# USBC_PD_PWR.net
KiCad netlist of a schematic drawn in Altium Designer
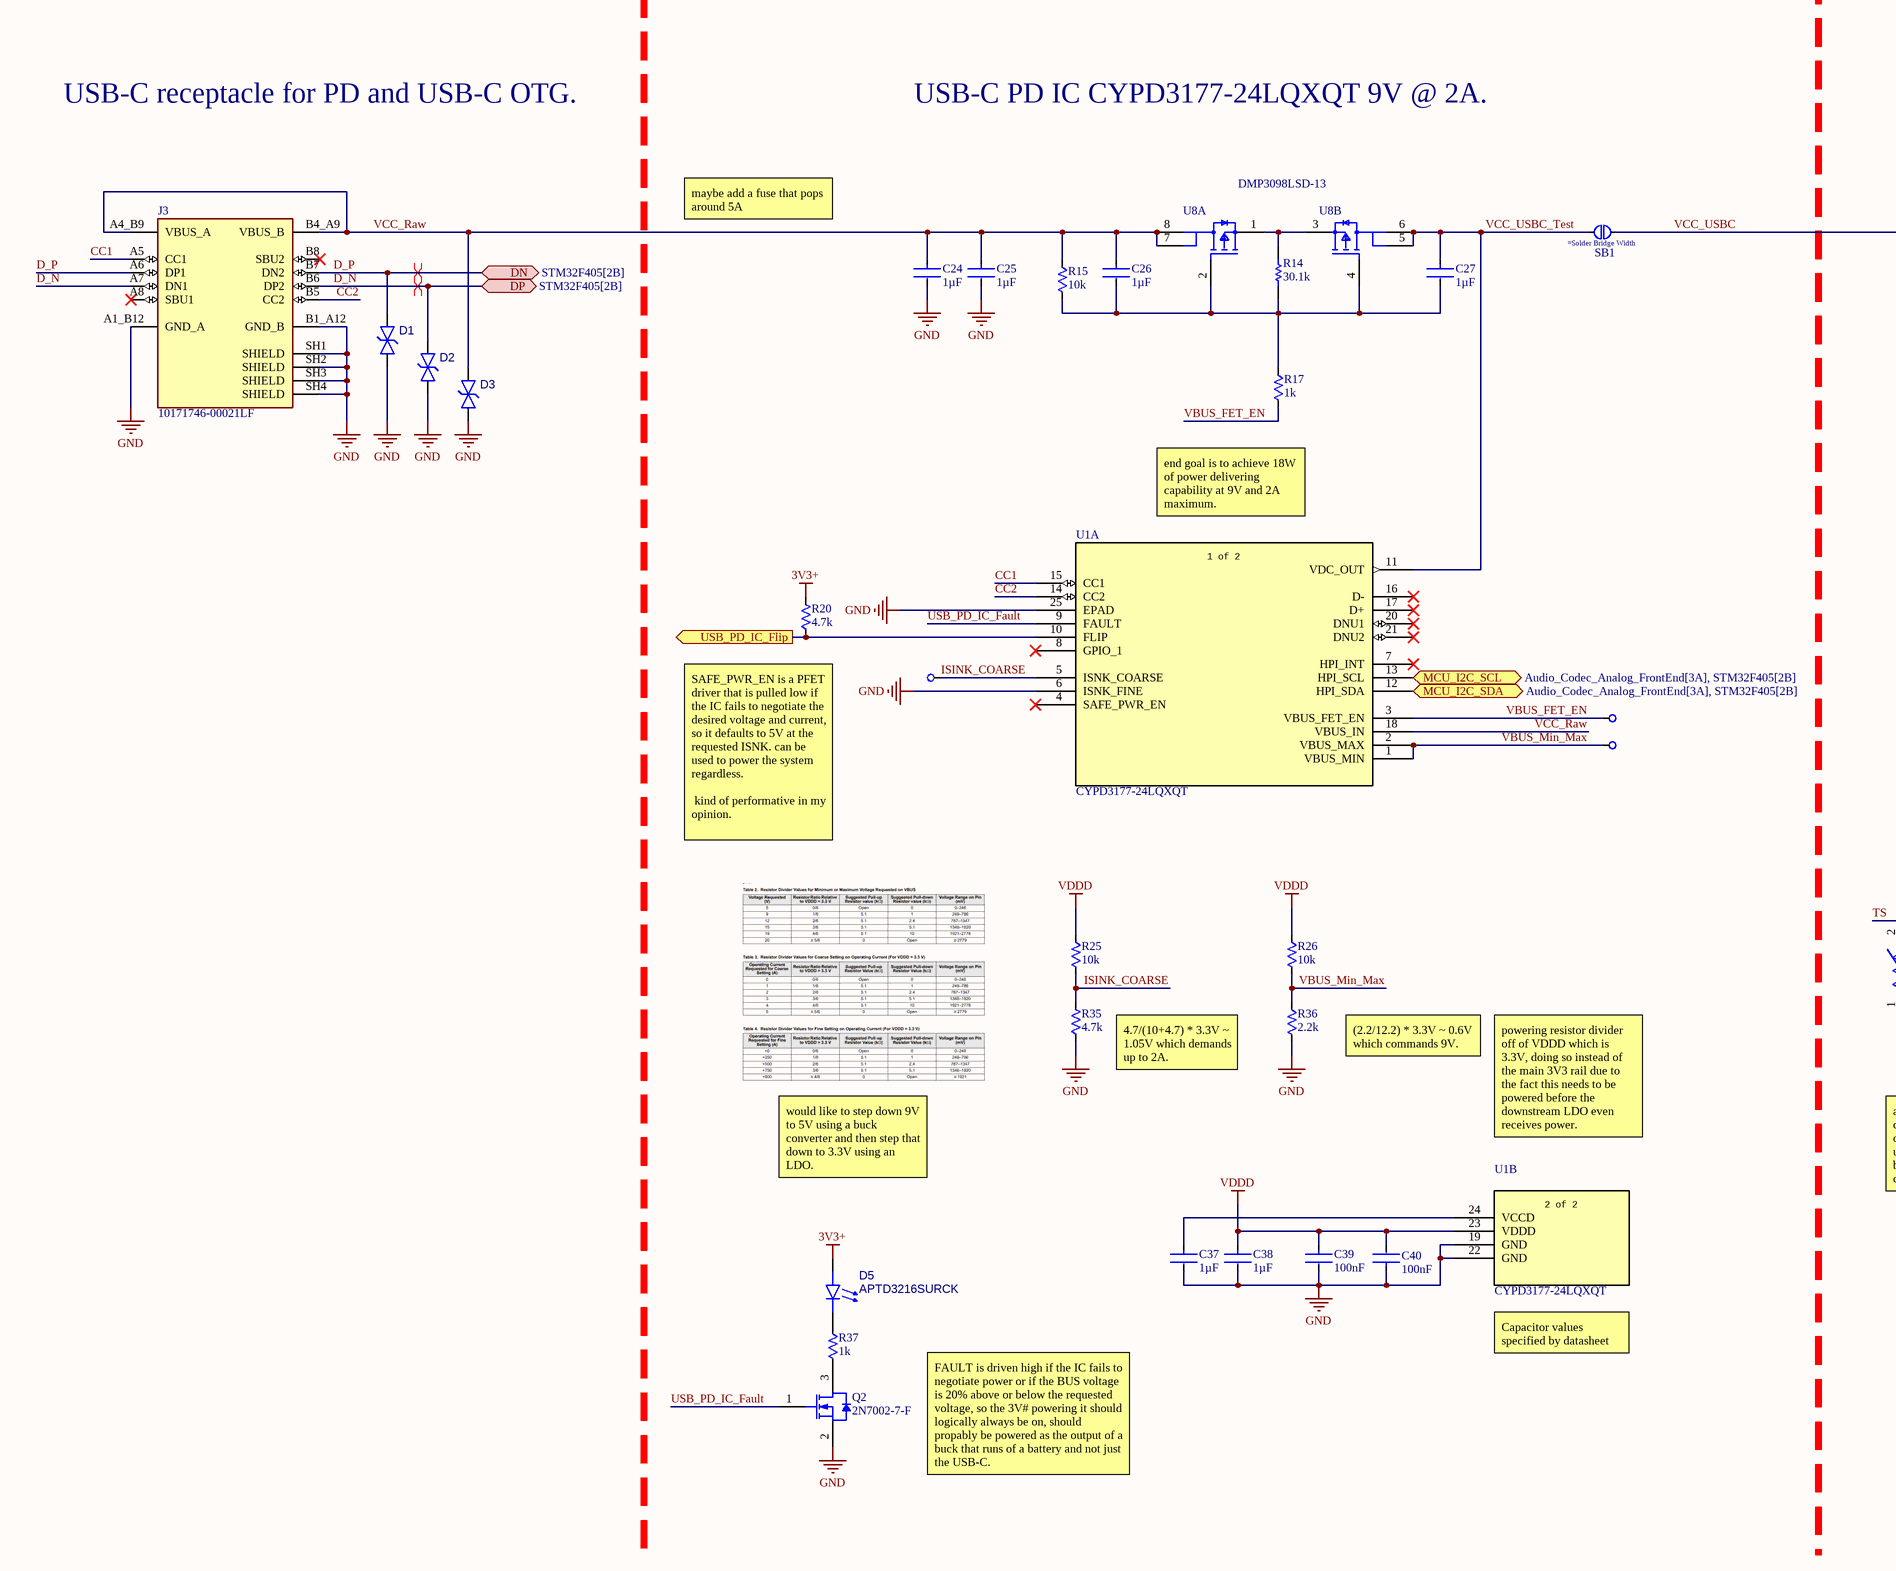
[diagram p0: USBC_PD_PWR.SchDoc, left]
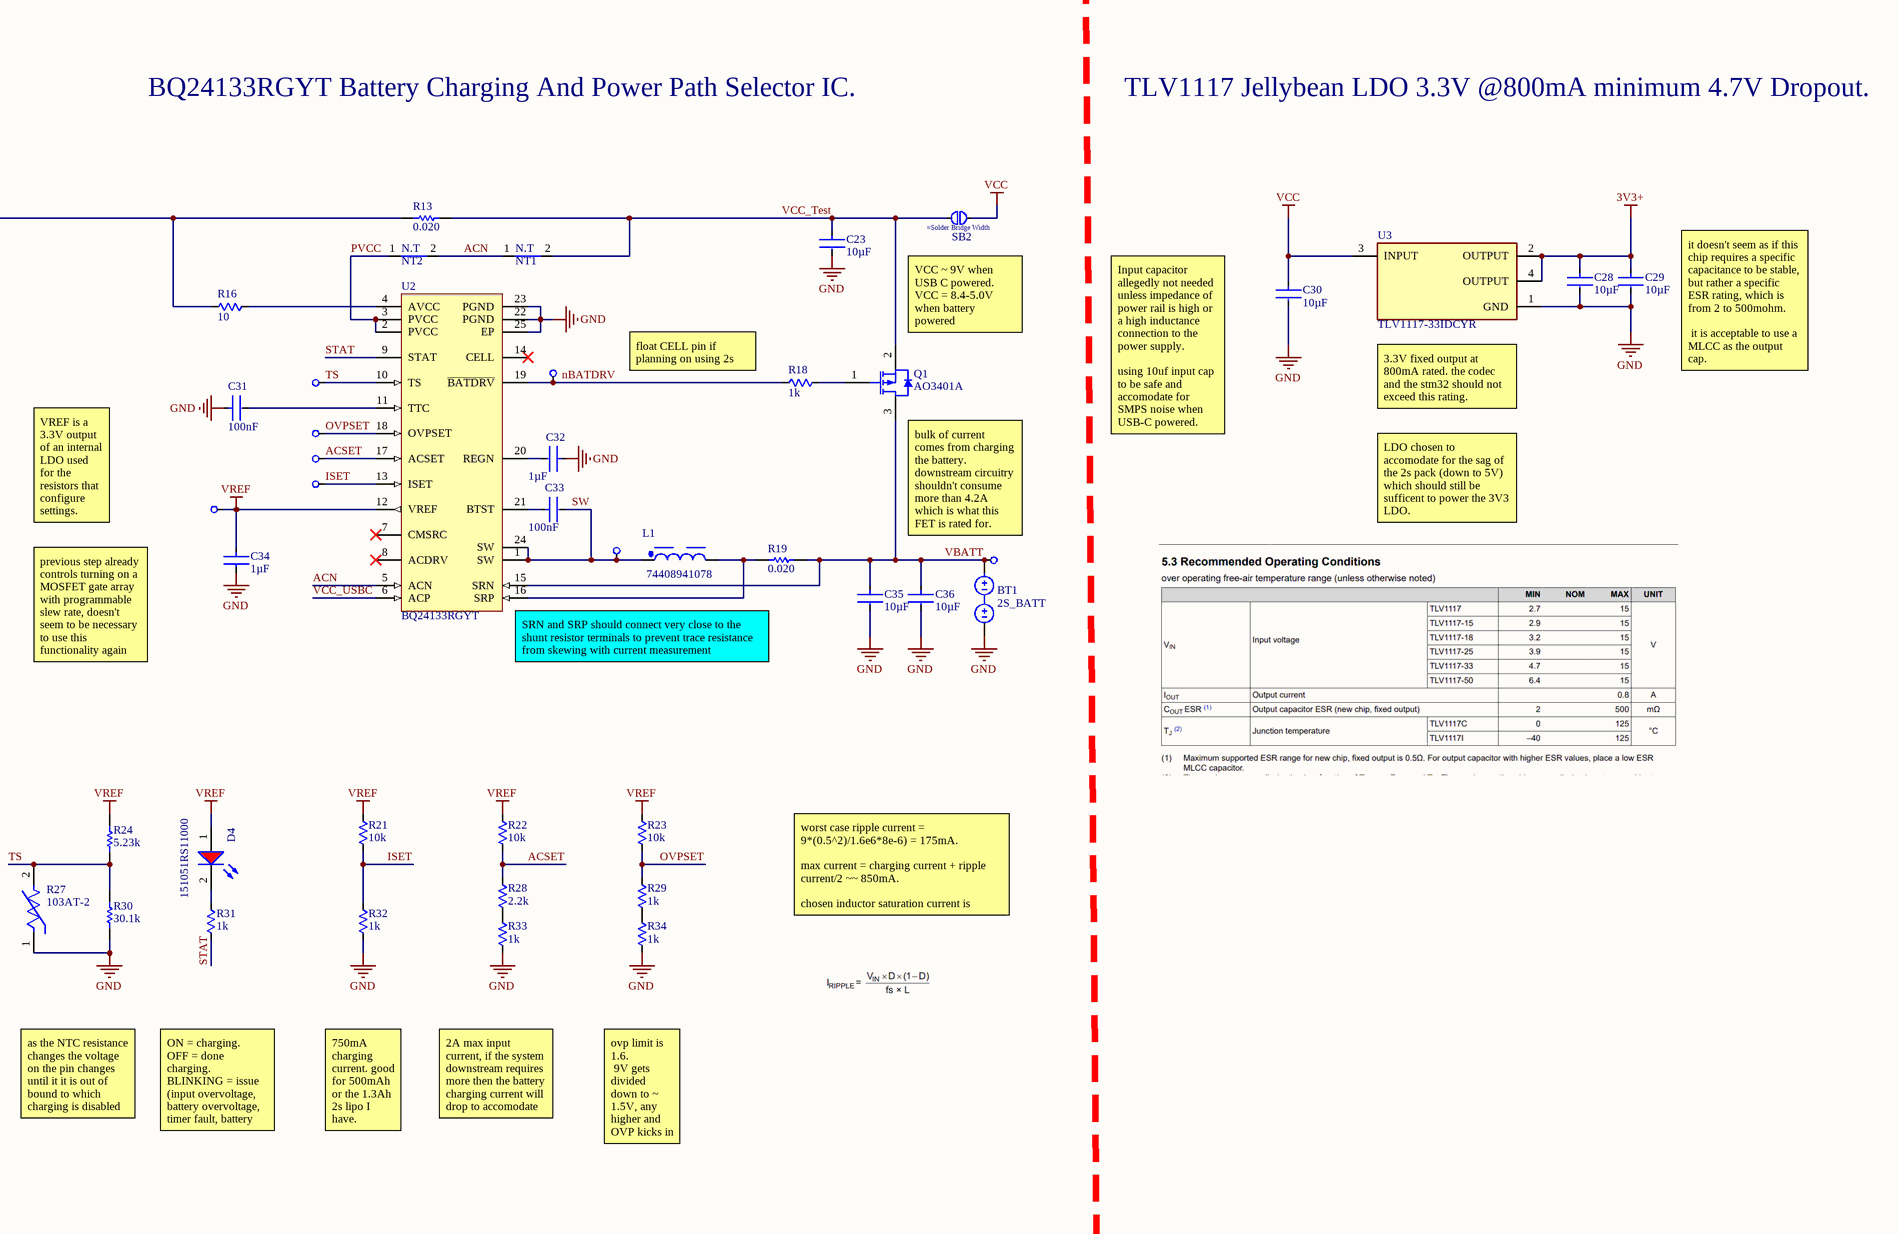
[diagram p1: USBC_PD_PWR.SchDoc, right]

(export (version "E")
  (design (tool "Eeschema 10.0.6"))
  (components
    (comp (ref "BT1")
      (value "2S_BATT")
      (footprint "2_soldering_pads")
      (libsource (lib "main_project_library") (part "2S_BATT"))
    )
    (comp (ref "C23")
      (value "10µF")
      (footprint "MURATA-G_M21B")
      (description "10 µF ±10% 25V Ceramic Capacitor X7S 0805 (2012 Metric)")
      (fields (field (name "TOLERANCE") "10%") (field (name "Comment") "GCM21BC71E106KE36L"))
      (libsource (lib "UCalgary Racing") (part "CAPACITOR"))
    )
    (comp (ref "C24")
      (value "1µF")
      (footprint "MURATA-G_M188")
      (description "1 µF ±10% 25V Ceramic Capacitor X7R 0603 (1608 Metric)")
      (fields (field (name "TOLERANCE") "10%") (field (name "Comment") "GCM188R71E105KA64D"))
      (libsource (lib "UCalgary Racing") (part "CAPACITOR"))
    )
    (comp (ref "C25")
      (value "1µF")
      (footprint "MURATA-G_M188")
      (description "1 µF ±10% 25V Ceramic Capacitor X7R 0603 (1608 Metric)")
      (fields (field (name "TOLERANCE") "10%") (field (name "Comment") "GCM188R71E105KA64D"))
      (libsource (lib "UCalgary Racing") (part "CAPACITOR"))
    )
    (comp (ref "C26")
      (value "1µF")
      (footprint "MURATA-G_M188")
      (description "1 µF ±10% 25V Ceramic Capacitor X7R 0603 (1608 Metric)")
      (fields (field (name "TOLERANCE") "10%") (field (name "Comment") "GCM188R71E105KA64D"))
      (libsource (lib "UCalgary Racing") (part "CAPACITOR"))
    )
    (comp (ref "C27")
      (value "1µF")
      (footprint "MURATA-G_M188")
      (description "1 µF ±10% 25V Ceramic Capacitor X7R 0603 (1608 Metric)")
      (fields (field (name "TOLERANCE") "10%") (field (name "Comment") "GCM188R71E105KA64D"))
      (libsource (lib "UCalgary Racing") (part "CAPACITOR"))
    )
    (comp (ref "C28")
      (value "10µF")
      (footprint "MURATA-G_M21B")
      (description "10 µF ±10% 25V Ceramic Capacitor X7S 0805 (2012 Metric)")
      (fields (field (name "TOLERANCE") "10%") (field (name "Comment") "GCM21BC71E106KE36L"))
      (libsource (lib "UCalgary Racing") (part "CAPACITOR"))
    )
    (comp (ref "C29")
      (value "10µF")
      (footprint "MURATA-G_M21B")
      (description "10 µF ±10% 25V Ceramic Capacitor X7S 0805 (2012 Metric)")
      (fields (field (name "TOLERANCE") "10%") (field (name "Comment") "GCM21BC71E106KE36L"))
      (libsource (lib "UCalgary Racing") (part "CAPACITOR"))
    )
    (comp (ref "C30")
      (value "10µF")
      (footprint "MURATA-G_M21B")
      (description "10 µF ±10% 25V Ceramic Capacitor X7S 0805 (2012 Metric)")
      (fields (field (name "TOLERANCE") "10%") (field (name "Comment") "GCM21BC71E106KE36L"))
      (libsource (lib "UCalgary Racing") (part "CAPACITOR"))
    )
    (comp (ref "C31")
      (value "100nF")
      (footprint "MURATA-G_M188")
      (description "0.1 µF ±10% 50V Ceramic Capacitor X7R 0603 (1608 Metric)")
      (fields (field (name "TOLERANCE") "10%") (field (name "Comment") "GCM188R71H104KA57D"))
      (libsource (lib "UCalgary Racing") (part "CAPACITOR"))
    )
    (comp (ref "C32")
      (value "1µF")
      (footprint "MURATA-G_M188")
      (description "1 µF ±10% 25V Ceramic Capacitor X7R 0603 (1608 Metric)")
      (fields (field (name "TOLERANCE") "10%") (field (name "Comment") "GCM188R71E105KA64D"))
      (libsource (lib "UCalgary Racing") (part "CAPACITOR"))
    )
    (comp (ref "C33")
      (value "100nF")
      (footprint "MURATA-G_M188")
      (description "0.1 µF ±10% 50V Ceramic Capacitor X7R 0603 (1608 Metric)")
      (fields (field (name "TOLERANCE") "10%") (field (name "Comment") "GCM188R71H104KA57D"))
      (libsource (lib "UCalgary Racing") (part "CAPACITOR"))
    )
    (comp (ref "C34")
      (value "1µF")
      (footprint "MURATA-G_M188")
      (description "1 µF ±10% 25V Ceramic Capacitor X7R 0603 (1608 Metric)")
      (fields (field (name "TOLERANCE") "10%") (field (name "Comment") "GCM188R71E105KA64D"))
      (libsource (lib "UCalgary Racing") (part "CAPACITOR"))
    )
    (comp (ref "C35")
      (value "10µF")
      (footprint "MURATA-G_M21B")
      (description "10 µF ±10% 25V Ceramic Capacitor X7S 0805 (2012 Metric)")
      (fields (field (name "TOLERANCE") "10%") (field (name "Comment") "GCM21BC71E106KE36L"))
      (libsource (lib "UCalgary Racing") (part "CAPACITOR"))
    )
    (comp (ref "C36")
      (value "10µF")
      (footprint "MURATA-G_M21B")
      (description "10 µF ±10% 25V Ceramic Capacitor X7S 0805 (2012 Metric)")
      (fields (field (name "TOLERANCE") "10%") (field (name "Comment") "GCM21BC71E106KE36L"))
      (libsource (lib "UCalgary Racing") (part "CAPACITOR"))
    )
    (comp (ref "C37")
      (value "1µF")
      (footprint "MURATA-G_M188")
      (description "1 µF ±10% 25V Ceramic Capacitor X7R 0603 (1608 Metric)")
      (fields (field (name "TOLERANCE") "10%") (field (name "Comment") "GCM188R71E105KA64D"))
      (libsource (lib "UCalgary Racing") (part "CAPACITOR"))
    )
    (comp (ref "C38")
      (value "1µF")
      (footprint "MURATA-G_M188")
      (description "1 µF ±10% 25V Ceramic Capacitor X7R 0603 (1608 Metric)")
      (fields (field (name "TOLERANCE") "10%") (field (name "Comment") "GCM188R71E105KA64D"))
      (libsource (lib "UCalgary Racing") (part "CAPACITOR"))
    )
    (comp (ref "C39")
      (value "100nF")
      (footprint "MURATA-G_M188")
      (description "0.1 µF ±10% 50V Ceramic Capacitor X7R 0603 (1608 Metric)")
      (fields (field (name "TOLERANCE") "10%") (field (name "Comment") "GCM188R71H104KA57D"))
      (libsource (lib "UCalgary Racing") (part "CAPACITOR"))
    )
    (comp (ref "C40")
      (value "100nF")
      (footprint "MURATA-G_M188")
      (description "0.1 µF ±10% 50V Ceramic Capacitor X7R 0603 (1608 Metric)")
      (fields (field (name "TOLERANCE") "10%") (field (name "Comment") "GCM188R71H104KA57D"))
      (libsource (lib "UCalgary Racing") (part "CAPACITOR"))
    )
    (comp (ref "D1")
      (value "SD12C.TCT")
      (footprint "SDXXC.TCT")
      (description "24V Clamp 15A (8/20µs) Ipp Tvs Diode Surface Mount SOD-323")
      (libsource (lib "UCalgary Racing") (part "D-TVS-AA-2"))
    )
    (comp (ref "D2")
      (value "SD12C.TCT")
      (footprint "SDXXC.TCT")
      (description "24V Clamp 15A (8/20µs) Ipp Tvs Diode Surface Mount SOD-323")
      (libsource (lib "UCalgary Racing") (part "D-TVS-AA-2"))
    )
    (comp (ref "D3")
      (value "SD12C.TCT")
      (footprint "SDXXC.TCT")
      (description "24V Clamp 15A (8/20µs) Ipp Tvs Diode Surface Mount SOD-323")
      (libsource (lib "UCalgary Racing") (part "D-TVS-AA-2"))
    )
    (comp (ref "D4")
      (value "151051RS11000")
      (footprint "WL-TMRC_D5.9H8.7")
      (description "WL-TMRC Red Color Diffused 5 mm Round Through Hole LED")
      (libsource (lib "Altium Content Vault") (part "LED_Red_1A-2K"))
    )
    (comp (ref "D5")
      (value "APTD3216SURCK")
      (footprint "APTD3216SURCK-Footprint-1")
      (description "Single Color LED, Hyper Red, Water Clear, 1.6mm")
      (libsource (lib "UCalgary Racing") (part "DIODE-LED-2"))
    )
    (comp (ref "J3")
      (value "10171746-00021LF")
      (footprint "AMPHENOL_10171746-00021LF")
      (fields (field (name "MF") "Amphenol"))
      (libsource (lib "UCalgary Racing") (part "10171746-00021LF"))
    )
    (comp (ref "L1")
      (value "74408941078")
      (footprint "WE-SPC_4818")
      (description "WE-SPC SMT Shielded Power Inductor")
      (libsource (lib "Altium Content Vault") (part "Inductor - 2"))
    )
    (comp (ref "NT1")
      (value "Net_Tie")
      (footprint "Net_Tie_150")
      (libsource (lib "main_project_library") (part "Net_Tie"))
    )
    (comp (ref "NT2")
      (value "Net_Tie")
      (footprint "Net_Tie_150")
      (libsource (lib "main_project_library") (part "Net_Tie"))
    )
    (comp (ref "Q1")
      (value "AO3401A")
      (footprint "AO-SOT-23-3L_V")
      (description "P-Channel MOSFET, 30 V, 4 A, -55 to 150 degC, 3-Pin SOT-23-3L, RoHS, Tape and Reel")
      (fields (field (name "MANUFACTURER") "Alpha and Omega"))
      (libsource (lib "Altium Content Vault") (part "PEMOS-GSD-3"))
    )
    (comp (ref "Q2")
      (value "2N7002-7-F")
      (footprint "DIODESINC-SOT23")
      (description "N-Channel 60 V 115mA (Ta) 370mW (Ta) Surface Mount SOT-23-3")
      (libsource (lib "UCalgary Racing") (part "NMOS_A"))
    )
    (comp (ref "R13")
      (value "0.020")
      (footprint "RESC3216X70X50LL05T20")
      (fields (field (name "MANUFACTURER") "Panasonic") (field (name "PART NUMBER") "ERJ8CWFR020V"))
      (libsource (lib "Altium Content Vault") (part "RES"))
    )
    (comp (ref "R14")
      (value "30.1k")
      (footprint "RESC0603(1608)_N")
      (description "30K1 0.1W 1% 0603 (1608 Metric)  SMD")
      (fields (field (name "TOLERANCE") "1 %") (field (name "POWER") "0.1 W"))
      (libsource (lib "Altium Content Vault") (part "RES"))
    )
    (comp (ref "R15")
      (value "10k")
      (footprint "VISHAY-CRCW0603")
      (description "10 kOhms ±1% 0.1W, 1/10W Chip Resistor 0603 (1608 Metric) Automotive AEC-Q200 Thick Film")
      (fields (field (name "POWER") "100mW") (field (name "TOLERANCE") "1%"))
      (libsource (lib "UCalgary Racing") (part "RESISTOR"))
    )
    (comp (ref "R16")
      (value "10")
      (footprint "FP-CRCW1206-e3-MFG")
      (description "RES SMD 10 OHM 1% 3/4W 1206")
      (fields (field (name "POWER") "750mW") (field (name "TOLERANCE") "1%"))
      (libsource (lib "UCalgary Racing") (part "RESISTOR"))
    )
    (comp (ref "R17")
      (value "1k")
      (footprint "VISHAY-TNPW0603")
      (fields
        (field (name "POWER") "100mW")
        (field (name "TOLERANCE") "0.1%")
        (field (name "Comment") "TNPW06031K00BEEA")
      )
      (libsource (lib "UCalgary Racing") (part "RESISTOR"))
    )
    (comp (ref "R18")
      (value "1k")
      (footprint "VISHAY-TNPW0603")
      (fields
        (field (name "POWER") "100mW")
        (field (name "TOLERANCE") "0.1%")
        (field (name "Comment") "TNPW06031K00BEEA")
      )
      (libsource (lib "UCalgary Racing") (part "RESISTOR"))
    )
    (comp (ref "R19")
      (value "0.020")
      (footprint "RESC3216X70X50LL05T20")
      (fields (field (name "MANUFACTURER") "Panasonic") (field (name "PART NUMBER") "ERJ8CWFR020V"))
      (libsource (lib "Altium Content Vault") (part "RES"))
    )
    (comp (ref "R20")
      (value "4.7k")
      (footprint "VISHAY-CRCW0603")
      (description "4.7 kOhms ±1% 0.1W, 1/10W Chip Resistor 0603 (1608 Metric) Automotive AEC-Q200 Thick Film")
      (fields (field (name "POWER") "100mW") (field (name "TOLERANCE") "1%"))
      (libsource (lib "UCalgary Racing") (part "RESISTOR"))
    )
    (comp (ref "R21")
      (value "10k")
      (footprint "VISHAY-CRCW0603")
      (description "10 kOhms ±1% 0.1W, 1/10W Chip Resistor 0603 (1608 Metric) Automotive AEC-Q200 Thick Film")
      (fields (field (name "POWER") "100mW") (field (name "TOLERANCE") "1%"))
      (libsource (lib "UCalgary Racing") (part "RESISTOR"))
    )
    (comp (ref "R22")
      (value "10k")
      (footprint "VISHAY-CRCW0603")
      (description "10 kOhms ±1% 0.1W, 1/10W Chip Resistor 0603 (1608 Metric) Automotive AEC-Q200 Thick Film")
      (fields (field (name "POWER") "100mW") (field (name "TOLERANCE") "1%"))
      (libsource (lib "UCalgary Racing") (part "RESISTOR"))
    )
    (comp (ref "R23")
      (value "10k")
      (footprint "VISHAY-CRCW0603")
      (description "10 kOhms ±1% 0.1W, 1/10W Chip Resistor 0603 (1608 Metric) Automotive AEC-Q200 Thick Film")
      (fields (field (name "POWER") "100mW") (field (name "TOLERANCE") "1%"))
      (libsource (lib "UCalgary Racing") (part "RESISTOR"))
    )
    (comp (ref "R24")
      (value "5.23k")
      (footprint "RESC1608X55X30NL15T15")
      (fields (field (name "MANUFACTURER") "Panasonic") (field (name "PART NUMBER") "ERJ-3EKF5231V"))
      (libsource (lib "Altium Content Vault") (part "RES"))
    )
    (comp (ref "R25")
      (value "10k")
      (footprint "VISHAY-CRCW0603")
      (description "10 kOhms ±1% 0.1W, 1/10W Chip Resistor 0603 (1608 Metric) Automotive AEC-Q200 Thick Film")
      (fields (field (name "POWER") "100mW") (field (name "TOLERANCE") "1%"))
      (libsource (lib "UCalgary Racing") (part "RESISTOR"))
    )
    (comp (ref "R26")
      (value "10k")
      (footprint "VISHAY-CRCW0603")
      (description "10 kOhms ±1% 0.1W, 1/10W Chip Resistor 0603 (1608 Metric) Automotive AEC-Q200 Thick Film")
      (fields (field (name "POWER") "100mW") (field (name "TOLERANCE") "1%"))
      (libsource (lib "UCalgary Racing") (part "RESISTOR"))
    )
    (comp (ref "R27")
      (value "103AT-2")
      (footprint "FP-103AT-2-MFG")
      (description "Thermistor NTC 10KOhm 1% 2-Pin")
      (fields (field (name "TOLERANCE") "1%"))
      (libsource (lib "Altium Content Vault") (part "3b148a6ebabc5fb4d708a66c052d352"))
    )
    (comp (ref "R28")
      (value "2.2k")
      (footprint "VISHAY-CRCW0603")
      (description "2.2 kOhms ±1% 0.1W, 1/10W Chip Resistor 0603 (1608 Metric) Automotive AEC-Q200 Thick Film")
      (fields (field (name "TOLERANCE") "1%") (field (name "POWER") "100mW"))
      (libsource (lib "UCalgary Racing") (part "RESISTOR"))
    )
    (comp (ref "R29")
      (value "1k")
      (footprint "VISHAY-TNPW0603")
      (fields
        (field (name "POWER") "100mW")
        (field (name "TOLERANCE") "0.1%")
        (field (name "Comment") "TNPW06031K00BEEA")
      )
      (libsource (lib "UCalgary Racing") (part "RESISTOR"))
    )
    (comp (ref "R30")
      (value "30.1k")
      (footprint "RESC0603(1608)_N")
      (description "30K1 0.1W 1% 0603 (1608 Metric)  SMD")
      (fields (field (name "TOLERANCE") "1 %") (field (name "POWER") "0.1 W"))
      (libsource (lib "Altium Content Vault") (part "RES"))
    )
    (comp (ref "R31")
      (value "1k")
      (footprint "VISHAY-TNPW0603")
      (fields
        (field (name "POWER") "100mW")
        (field (name "TOLERANCE") "0.1%")
        (field (name "Comment") "TNPW06031K00BEEA")
      )
      (libsource (lib "UCalgary Racing") (part "RESISTOR"))
    )
    (comp (ref "R32")
      (value "1k")
      (footprint "VISHAY-TNPW0603")
      (fields
        (field (name "POWER") "100mW")
        (field (name "TOLERANCE") "0.1%")
        (field (name "Comment") "TNPW06031K00BEEA")
      )
      (libsource (lib "UCalgary Racing") (part "RESISTOR"))
    )
    (comp (ref "R33")
      (value "1k")
      (footprint "VISHAY-TNPW0603")
      (fields
        (field (name "POWER") "100mW")
        (field (name "TOLERANCE") "0.1%")
        (field (name "Comment") "TNPW06031K00BEEA")
      )
      (libsource (lib "UCalgary Racing") (part "RESISTOR"))
    )
    (comp (ref "R34")
      (value "1k")
      (footprint "VISHAY-TNPW0603")
      (fields
        (field (name "POWER") "100mW")
        (field (name "TOLERANCE") "0.1%")
        (field (name "Comment") "TNPW06031K00BEEA")
      )
      (libsource (lib "UCalgary Racing") (part "RESISTOR"))
    )
    (comp (ref "R35")
      (value "4.7k")
      (footprint "VISHAY-CRCW0603")
      (description "4.7 kOhms ±1% 0.1W, 1/10W Chip Resistor 0603 (1608 Metric) Automotive AEC-Q200 Thick Film")
      (fields (field (name "POWER") "100mW") (field (name "TOLERANCE") "1%"))
      (libsource (lib "UCalgary Racing") (part "RESISTOR"))
    )
    (comp (ref "R36")
      (value "2.2k")
      (footprint "VISHAY-CRCW0603")
      (description "2.2 kOhms ±1% 0.1W, 1/10W Chip Resistor 0603 (1608 Metric) Automotive AEC-Q200 Thick Film")
      (fields (field (name "TOLERANCE") "1%") (field (name "POWER") "100mW"))
      (libsource (lib "UCalgary Racing") (part "RESISTOR"))
    )
    (comp (ref "R37")
      (value "1k")
      (footprint "VISHAY-TNPW0603")
      (fields
        (field (name "POWER") "100mW")
        (field (name "TOLERANCE") "0.1%")
        (field (name "Comment") "TNPW06031K00BEEA")
      )
      (libsource (lib "UCalgary Racing") (part "RESISTOR"))
    )
    (comp (ref "SB1")
      (value "SOLDER_BRIDGE")
      (footprint "SOLDER_BRIDGE_60MIL")
      (description "Various 2-pad solder bridge footprints")
      (libsource (lib "UCalgary Racing") (part "SOLDER_BRIDGE_SYMBOL"))
    )
    (comp (ref "SB2")
      (value "SOLDER_BRIDGE")
      (footprint "SOLDER_BRIDGE_60MIL")
      (description "Various 2-pad solder bridge footprints")
      (libsource (lib "UCalgary Racing") (part "SOLDER_BRIDGE_SYMBOL"))
    )
    (comp (ref "TP14")
      (value "Testpoint 1mm")
      (footprint "Testpoint 1mm")
      (description "Labelled 1mm testpoint pad")
      (libsource (lib "UCalgary Racing") (part "Testpoint 1mm"))
    )
    (comp (ref "TP15")
      (value "Testpoint 1mm")
      (footprint "Testpoint 1mm")
      (description "Labelled 1mm testpoint pad")
      (libsource (lib "UCalgary Racing") (part "Testpoint 1mm"))
    )
    (comp (ref "TP16")
      (value "Testpoint 1mm")
      (footprint "Testpoint 1mm")
      (description "Labelled 1mm testpoint pad")
      (libsource (lib "UCalgary Racing") (part "Testpoint 1mm"))
    )
    (comp (ref "TP17")
      (value "Testpoint 1mm")
      (footprint "Testpoint 1mm")
      (description "Labelled 1mm testpoint pad")
      (libsource (lib "UCalgary Racing") (part "Testpoint 1mm"))
    )
    (comp (ref "TP18")
      (value "Testpoint 1mm")
      (footprint "Testpoint 1mm")
      (description "Labelled 1mm testpoint pad")
      (libsource (lib "UCalgary Racing") (part "Testpoint 1mm"))
    )
    (comp (ref "TP19")
      (value "Testpoint 1mm")
      (footprint "Testpoint 1mm")
      (description "Labelled 1mm testpoint pad")
      (libsource (lib "UCalgary Racing") (part "Testpoint 1mm"))
    )
    (comp (ref "TP20")
      (value "Testpoint 1mm")
      (footprint "Testpoint 1mm")
      (description "Labelled 1mm testpoint pad")
      (libsource (lib "UCalgary Racing") (part "Testpoint 1mm"))
    )
    (comp (ref "TP21")
      (value "Testpoint 1mm")
      (footprint "Testpoint 1mm")
      (description "Labelled 1mm testpoint pad")
      (libsource (lib "UCalgary Racing") (part "Testpoint 1mm"))
    )
    (comp (ref "TP22")
      (value "Testpoint 1mm")
      (footprint "Testpoint 1mm")
      (description "Labelled 1mm testpoint pad")
      (libsource (lib "UCalgary Racing") (part "Testpoint 1mm"))
    )
    (comp (ref "TP23")
      (value "Testpoint 1mm")
      (footprint "Testpoint 1mm")
      (description "Labelled 1mm testpoint pad")
      (libsource (lib "UCalgary Racing") (part "Testpoint 1mm"))
    )
    (comp (ref "TP24")
      (value "Testpoint 1mm")
      (footprint "Testpoint 1mm")
      (description "Labelled 1mm testpoint pad")
      (libsource (lib "UCalgary Racing") (part "Testpoint 1mm"))
    )
    (comp (ref "U1")
      (value "CYPD3177-24LQXQT")
      (footprint "main_PCB_library:QFN24_CYPD3177-24LQXQT_INF")
      (fields (field (name "COPYRIGHT") "Copyright (C) 2026 Ultra Librarian. All rights reserved."))
      (libsource (lib "main_project_library") (part "CYPD3177-24LQXQT"))
    )
    (comp (ref "U2")
      (value "BQ24133RGYT")
      (footprint "RGY0024A_V")
      (fields (field (name "MANUFACTURER") "Texas Instruments"))
      (libsource (lib "Altium Content Vault") (part "TI-BQ24133RGY24-3100X2050TP"))
    )
    (comp (ref "U3")
      (value "TLV1117-33IDCYR")
      (footprint "FP-DCY0004A-MFG")
      (description "IC REG LIN 3.3V 800MA SOT223-4")
      (fields
        (field (name "MANUFACTURER") "Texas Instruments")
        (field (name "OCTOPART") "https://octopart.com/tlv1117-33idcyr-texas+instruments-669250")
      )
      (libsource (lib "Altium Content Vault") (part "d420fb9686013fb832e66295cdf4acf"))
    )
    (comp (ref "U8")
      (value "DMP3098LSD-13")
      (footprint "SOP_DMP3098LSD-13_DIO")
      (description "Description")
      (fields (field (name "COPYRIGHT") "Copyright (C) 2025 Ultra Librarian. All rights reserved."))
      (libsource (lib "main_project_library") (part "DMP3098LSD-13"))
    )
  )
  (nets
    (net (code "1") (name "/ACN") (class "Default")
      (node (ref "NT1") (pin "1") (pinfunction "1_1") (pintype "passive"))
      (node (ref "NT2") (pin "2") (pinfunction "2_2") (pintype "passive"))
      (node (ref "U2") (pin "5") (pinfunction "ACN_5") (pintype "input"))
    )
    (net (code "2") (name "/ACSET") (class "Default")
      (node (ref "R22") (pin "1") (pinfunction "1_1") (pintype "passive"))
      (node (ref "R28") (pin "2") (pinfunction "2_2") (pintype "passive"))
      (node (ref "TP17") (pin "1") (pinfunction "1_1") (pintype "passive"))
      (node (ref "U2") (pin "17") (pinfunction "ACSET_17") (pintype "input"))
    )
    (net (code "3") (name "/CC1") (class "Default")
      (node (ref "J3") (pin "A5") (pinfunction "CC1_A5") (pintype "bidirectional"))
      (node (ref "U1") (pin "15") (pinfunction "CC1_15") (pintype "bidirectional"))
    )
    (net (code "4") (name "/CC2") (class "Default")
      (node (ref "J3") (pin "B5") (pinfunction "CC2_B5") (pintype "bidirectional"))
      (node (ref "U1") (pin "14") (pinfunction "CC2_14") (pintype "bidirectional"))
    )
    (net (code "5") (name "/D_N") (class "Default")
      (node (ref "D2") (pin "2") (pinfunction "A_2") (pintype "passive"))
      (node (ref "J3") (pin "A7") (pinfunction "DN1_A7") (pintype "bidirectional"))
      (node (ref "J3") (pin "B6") (pinfunction "DP2_B6") (pintype "bidirectional"))
    )
    (net (code "6") (name "/D_P") (class "Default")
      (node (ref "D1") (pin "2") (pinfunction "A_2") (pintype "passive"))
      (node (ref "J3") (pin "A6") (pinfunction "DP1_A6") (pintype "bidirectional"))
      (node (ref "J3") (pin "B7") (pinfunction "DN2_B7") (pintype "bidirectional"))
    )
    (net (code "7") (name "/ISET") (class "Default")
      (node (ref "R21") (pin "1") (pinfunction "1_1") (pintype "passive"))
      (node (ref "R32") (pin "2") (pinfunction "2_2") (pintype "passive"))
      (node (ref "TP18") (pin "1") (pinfunction "1_1") (pintype "passive"))
      (node (ref "U2") (pin "13") (pinfunction "ISET_13") (pintype "input"))
    )
    (net (code "8") (name "/ISINK_COARSE") (class "Default")
      (node (ref "R25") (pin "1") (pinfunction "1_1") (pintype "passive"))
      (node (ref "R35") (pin "1") (pinfunction "1_1") (pintype "passive"))
      (node (ref "TP22") (pin "1") (pinfunction "1_1") (pintype "passive"))
      (node (ref "U1") (pin "5") (pinfunction "ISNK_COARSE_5") (pintype "passive"))
    )
    (net (code "9") (name "/MCU_I2C_SCL") (class "Default")
      (node (ref "U1") (pin "13") (pinfunction "HPI_SCL_13") (pintype "passive"))
    )
    (net (code "10") (name "/MCU_I2C_SDA") (class "Default")
      (node (ref "U1") (pin "12") (pinfunction "HPI_SDA_12") (pintype "passive"))
    )
    (net (code "11") (name "/OVPSET") (class "Default")
      (node (ref "R23") (pin "1") (pinfunction "1_1") (pintype "passive"))
      (node (ref "R29") (pin "2") (pinfunction "2_2") (pintype "passive"))
      (node (ref "TP16") (pin "1") (pinfunction "1_1") (pintype "passive"))
      (node (ref "U2") (pin "18") (pinfunction "OVPSET_18") (pintype "input"))
    )
    (net (code "12") (name "/PVCC") (class "Default")
      (node (ref "NT2") (pin "1") (pinfunction "1_1") (pintype "passive"))
      (node (ref "U2") (pin "2") (pinfunction "PVCC_2") (pintype "power_in"))
      (node (ref "U2") (pin "3") (pinfunction "PVCC_3") (pintype "power_in"))
    )
    (net (code "13") (name "/STAT") (class "Default")
      (node (ref "R31") (pin "1") (pinfunction "1_1") (pintype "passive"))
      (node (ref "U2") (pin "9") (pinfunction "STAT_9") (pintype "tri_state"))
    )
    (net (code "14") (name "/SW") (class "Default")
      (node (ref "C33") (pin "2") (pinfunction "2_2") (pintype "passive"))
      (node (ref "L1") (pin "1") (pinfunction "1_1") (pintype "passive"))
      (node (ref "TP20") (pin "1") (pinfunction "1_1") (pintype "passive"))
      (node (ref "U2") (pin "1") (pinfunction "SW_1") (pintype "power_in"))
      (node (ref "U2") (pin "24") (pinfunction "SW_24") (pintype "power_in"))
    )
    (net (code "15") (name "/TS") (class "Default")
      (node (ref "R24") (pin "1") (pinfunction "1_1") (pintype "passive"))
      (node (ref "R27") (pin "2") (pinfunction "2_2") (pintype "passive"))
      (node (ref "R30") (pin "2") (pinfunction "2_2") (pintype "passive"))
      (node (ref "TP15") (pin "1") (pinfunction "1_1") (pintype "passive"))
      (node (ref "U2") (pin "10") (pinfunction "TS_10") (pintype "input"))
    )
    (net (code "16") (name "/USB_PD_IC_Fault") (class "Default")
      (node (ref "Q2") (pin "1") (pinfunction "G_1") (pintype "passive"))
      (node (ref "U1") (pin "9") (pinfunction "FAULT_9") (pintype "passive"))
    )
    (net (code "17") (name "/USB_PD_IC_Flip") (class "Default")
      (node (ref "R20") (pin "2") (pinfunction "2_2") (pintype "passive"))
      (node (ref "U1") (pin "10") (pinfunction "FLIP_10") (pintype "passive"))
    )
    (net (code "18") (name "/VBATT") (class "Default")
      (node (ref "BT1") (pin "1") (pinfunction "1_1") (pintype "passive"))
      (node (ref "C35") (pin "1") (pinfunction "1_1") (pintype "passive"))
      (node (ref "C36") (pin "1") (pinfunction "1_1") (pintype "passive"))
      (node (ref "Q1") (pin "3") (pinfunction "DRAIN_3") (pintype "passive"))
      (node (ref "R19") (pin "2") (pinfunction "2_2") (pintype "passive"))
      (node (ref "TP21") (pin "1") (pinfunction "1_1") (pintype "passive"))
      (node (ref "U2") (pin "15") (pinfunction "SRN_15") (pintype "input"))
    )
    (net (code "19") (name "/VBUS_FET_EN") (class "Default")
      (node (ref "R17") (pin "1") (pinfunction "1_1") (pintype "passive"))
      (node (ref "TP23") (pin "1") (pinfunction "1_1") (pintype "passive"))
      (node (ref "U1") (pin "3") (pinfunction "VBUS_FET_EN_3") (pintype "passive"))
    )
    (net (code "20") (name "/VBUS_Min_Max") (class "Default")
      (node (ref "R26") (pin "1") (pinfunction "1_1") (pintype "passive"))
      (node (ref "R36") (pin "2") (pinfunction "2_2") (pintype "passive"))
      (node (ref "TP24") (pin "1") (pinfunction "1_1") (pintype "passive"))
      (node (ref "U1") (pin "1") (pinfunction "VBUS_MIN_1") (pintype "passive"))
      (node (ref "U1") (pin "2") (pinfunction "VBUS_MAX_2") (pintype "passive"))
    )
    (net (code "21") (name "/VCC_Raw") (class "Default")
      (node (ref "C24") (pin "1") (pinfunction "1_1") (pintype "passive"))
      (node (ref "C25") (pin "1") (pinfunction "1_1") (pintype "passive"))
      (node (ref "C26") (pin "1") (pinfunction "1_1") (pintype "passive"))
      (node (ref "D3") (pin "2") (pinfunction "A_2") (pintype "passive"))
      (node (ref "J3") (pin "A4_B9") (pinfunction "VBUS_A_A4_B9") (pintype "power_in"))
      (node (ref "J3") (pin "B4_A9") (pinfunction "VBUS_B_B4_A9") (pintype "power_in"))
      (node (ref "R15") (pin "2") (pinfunction "2_2") (pintype "passive"))
      (node (ref "U1") (pin "18") (pinfunction "VBUS_IN_18") (pintype "passive"))
      (node (ref "U8") (pin "7") (pinfunction "D1_7") (pintype "passive"))
      (node (ref "U8") (pin "8") (pinfunction "D1_8") (pintype "passive"))
    )
    (net (code "22") (name "/VCC_Test") (class "Default")
      (node (ref "C23") (pin "1") (pinfunction "1_1") (pintype "passive"))
      (node (ref "NT1") (pin "2") (pinfunction "2_2") (pintype "passive"))
      (node (ref "Q1") (pin "2") (pinfunction "SOURCE_2") (pintype "passive"))
      (node (ref "R13") (pin "2") (pinfunction "2_2") (pintype "passive"))
      (node (ref "SB2") (pin "1") (pinfunction "1_1") (pintype "passive"))
    )
    (net (code "23") (name "/VCC_USBC") (class "Default")
      (node (ref "R13") (pin "1") (pinfunction "1_1") (pintype "passive"))
      (node (ref "R16") (pin "1") (pinfunction "1_1") (pintype "passive"))
      (node (ref "SB1") (pin "2") (pinfunction "2_2") (pintype "passive"))
      (node (ref "U2") (pin "6") (pinfunction "ACP_6") (pintype "input"))
    )
    (net (code "24") (name "/VCC_USBC_Test") (class "Default")
      (node (ref "C27") (pin "1") (pinfunction "1_1") (pintype "passive"))
      (node (ref "SB1") (pin "1") (pinfunction "1_1") (pintype "passive"))
      (node (ref "U1") (pin "11") (pinfunction "VDC_OUT_11") (pintype "output"))
      (node (ref "U8") (pin "5") (pinfunction "D2_5") (pintype "passive"))
      (node (ref "U8") (pin "6") (pinfunction "D2_6") (pintype "passive"))
    )
    (net (code "25") (name "/nBATDRV") (class "Default")
      (node (ref "R18") (pin "2") (pinfunction "2_2") (pintype "passive"))
      (node (ref "TP14") (pin "1") (pinfunction "1_1") (pintype "passive"))
      (node (ref "U2") (pin "19") (pinfunction "~{BATDRV}_19") (pintype "passive"))
    )
    (net (code "26") (name "3V3+") (class "Default")
      (node (ref "C28") (pin "1") (pinfunction "1_1") (pintype "passive"))
      (node (ref "C29") (pin "1") (pinfunction "1_1") (pintype "passive"))
      (node (ref "D5") (pin "2") (pinfunction "A_2") (pintype "passive"))
      (node (ref "R20") (pin "1") (pinfunction "1_1") (pintype "passive"))
      (node (ref "U3") (pin "2") (pinfunction "OUTPUT_2") (pintype "power_in"))
      (node (ref "U3") (pin "4") (pinfunction "OUTPUT_4") (pintype "power_in"))
    )
    (net (code "27") (name "GND") (class "Default")
      (node (ref "BT1") (pin "2") (pinfunction "2_2") (pintype "passive"))
      (node (ref "C23") (pin "2") (pinfunction "2_2") (pintype "passive"))
      (node (ref "C24") (pin "2") (pinfunction "2_2") (pintype "passive"))
      (node (ref "C25") (pin "2") (pinfunction "2_2") (pintype "passive"))
      (node (ref "C28") (pin "2") (pinfunction "2_2") (pintype "passive"))
      (node (ref "C29") (pin "2") (pinfunction "2_2") (pintype "passive"))
      (node (ref "C30") (pin "2") (pinfunction "2_2") (pintype "passive"))
      (node (ref "C31") (pin "1") (pinfunction "1_1") (pintype "passive"))
      (node (ref "C32") (pin "1") (pinfunction "1_1") (pintype "passive"))
      (node (ref "C34") (pin "2") (pinfunction "2_2") (pintype "passive"))
      (node (ref "C35") (pin "2") (pinfunction "2_2") (pintype "passive"))
      (node (ref "C36") (pin "2") (pinfunction "2_2") (pintype "passive"))
      (node (ref "C37") (pin "2") (pinfunction "2_2") (pintype "passive"))
      (node (ref "C38") (pin "2") (pinfunction "2_2") (pintype "passive"))
      (node (ref "C39") (pin "2") (pinfunction "2_2") (pintype "passive"))
      (node (ref "C40") (pin "1") (pinfunction "1_1") (pintype "passive"))
      (node (ref "D1") (pin "1") (pinfunction "A_1") (pintype "passive"))
      (node (ref "D2") (pin "1") (pinfunction "A_1") (pintype "passive"))
      (node (ref "D3") (pin "1") (pinfunction "A_1") (pintype "passive"))
      (node (ref "J3") (pin "A1_B12") (pinfunction "GND_A_A1_B12") (pintype "power_in"))
      (node (ref "J3") (pin "B1_A12") (pinfunction "GND_B_B1_A12") (pintype "power_in"))
      (node (ref "J3") (pin "SH1") (pinfunction "SHIELD_SH1") (pintype "passive"))
      (node (ref "J3") (pin "SH2") (pinfunction "SHIELD_SH2") (pintype "passive"))
      (node (ref "J3") (pin "SH3") (pinfunction "SHIELD_SH3") (pintype "passive"))
      (node (ref "J3") (pin "SH4") (pinfunction "SHIELD_SH4") (pintype "passive"))
      (node (ref "Q2") (pin "2") (pinfunction "S_2") (pintype "passive"))
      (node (ref "R27") (pin "1") (pinfunction "1_1") (pintype "passive"))
      (node (ref "R30") (pin "1") (pinfunction "1_1") (pintype "passive"))
      (node (ref "R32") (pin "1") (pinfunction "1_1") (pintype "passive"))
      (node (ref "R33") (pin "1") (pinfunction "1_1") (pintype "passive"))
      (node (ref "R34") (pin "1") (pinfunction "1_1") (pintype "passive"))
      (node (ref "R35") (pin "2") (pinfunction "2_2") (pintype "passive"))
      (node (ref "R36") (pin "1") (pinfunction "1_1") (pintype "passive"))
      (node (ref "U1") (pin "19") (pinfunction "GND_19") (pintype "power_in"))
      (node (ref "U1") (pin "22") (pinfunction "GND_22") (pintype "power_in"))
      (node (ref "U1") (pin "25") (pinfunction "EPAD_25") (pintype "passive"))
      (node (ref "U1") (pin "6") (pinfunction "ISNK_FINE_6") (pintype "passive"))
      (node (ref "U2") (pin "22") (pinfunction "PGND_22") (pintype "power_in"))
      (node (ref "U2") (pin "23") (pinfunction "PGND_23") (pintype "power_in"))
      (node (ref "U2") (pin "25") (pinfunction "EP_25") (pintype "power_in"))
      (node (ref "U3") (pin "1") (pinfunction "GND_1") (pintype "power_in"))
    )
    (net (code "28") (name "Net-(D4-K)") (class "Default")
      (node (ref "D4") (pin "2") (pinfunction "K_2") (pintype "passive"))
      (node (ref "R31") (pin "2") (pinfunction "2_2") (pintype "passive"))
    )
    (net (code "29") (name "Net-(D5-K)") (class "Default")
      (node (ref "D5") (pin "1") (pinfunction "K_1") (pintype "passive"))
      (node (ref "R37") (pin "2") (pinfunction "2_2") (pintype "passive"))
    )
    (net (code "30") (name "Net-(Q1-GATE)") (class "Default")
      (node (ref "Q1") (pin "1") (pinfunction "GATE_1") (pintype "passive"))
      (node (ref "R18") (pin "1") (pinfunction "1_1") (pintype "passive"))
    )
    (net (code "31") (name "Net-(Q2-D)") (class "Default")
      (node (ref "Q2") (pin "3") (pinfunction "D_3") (pintype "passive"))
      (node (ref "R37") (pin "1") (pinfunction "1_1") (pintype "passive"))
    )
    (net (code "32") (name "Net-(R28-Pad1)") (class "Default")
      (node (ref "R28") (pin "1") (pinfunction "1_1") (pintype "passive"))
      (node (ref "R33") (pin "2") (pinfunction "2_2") (pintype "passive"))
    )
    (net (code "33") (name "Net-(R29-Pad1)") (class "Default")
      (node (ref "R29") (pin "1") (pinfunction "1_1") (pintype "passive"))
      (node (ref "R34") (pin "2") (pinfunction "2_2") (pintype "passive"))
    )
    (net (code "34") (name "Net-(U1B-VCCD)") (class "Default")
      (node (ref "C37") (pin "1") (pinfunction "1_1") (pintype "passive"))
      (node (ref "U1") (pin "24") (pinfunction "VCCD_24") (pintype "power_in"))
    )
    (net (code "35") (name "Net-(U2-AVCC)") (class "Default")
      (node (ref "R16") (pin "2") (pinfunction "2_2") (pintype "passive"))
      (node (ref "U2") (pin "4") (pinfunction "AVCC_4") (pintype "power_in"))
    )
    (net (code "36") (name "Net-(U2-BTST)") (class "Default")
      (node (ref "C33") (pin "1") (pinfunction "1_1") (pintype "passive"))
      (node (ref "U2") (pin "21") (pinfunction "BTST_21") (pintype "power_in"))
    )
    (net (code "37") (name "Net-(U2-REGN)") (class "Default")
      (node (ref "C32") (pin "2") (pinfunction "2_2") (pintype "passive"))
      (node (ref "U2") (pin "20") (pinfunction "REGN_20") (pintype "power_in"))
    )
    (net (code "38") (name "Net-(U2-SRP)") (class "Default")
      (node (ref "L1") (pin "2") (pinfunction "2_2") (pintype "passive"))
      (node (ref "R19") (pin "1") (pinfunction "1_1") (pintype "passive"))
      (node (ref "U2") (pin "16") (pinfunction "SRP_16") (pintype "input"))
    )
    (net (code "39") (name "Net-(U2-TTC)") (class "Default")
      (node (ref "C31") (pin "2") (pinfunction "2_2") (pintype "passive"))
      (node (ref "U2") (pin "11") (pinfunction "TTC_11") (pintype "input"))
    )
    (net (code "40") (name "Net-(U8A-G1)") (class "Default")
      (node (ref "C26") (pin "2") (pinfunction "2_2") (pintype "passive"))
      (node (ref "C27") (pin "2") (pinfunction "2_2") (pintype "passive"))
      (node (ref "R14") (pin "1") (pinfunction "1_1") (pintype "passive"))
      (node (ref "R15") (pin "1") (pinfunction "1_1") (pintype "passive"))
      (node (ref "R17") (pin "2") (pinfunction "2_2") (pintype "passive"))
      (node (ref "U8") (pin "2") (pinfunction "G1_2") (pintype "passive"))
      (node (ref "U8") (pin "4") (pinfunction "G2_4") (pintype "passive"))
    )
    (net (code "41") (name "Net-(U8A-S1)") (class "Default")
      (node (ref "R14") (pin "2") (pinfunction "2_2") (pintype "passive"))
      (node (ref "U8") (pin "1") (pinfunction "S1_1") (pintype "passive"))
      (node (ref "U8") (pin "3") (pinfunction "S2_3") (pintype "passive"))
    )
    (net (code "42") (name "VCC") (class "Default")
      (node (ref "C30") (pin "1") (pinfunction "1_1") (pintype "passive"))
      (node (ref "SB2") (pin "2") (pinfunction "2_2") (pintype "passive"))
      (node (ref "U3") (pin "3") (pinfunction "INPUT_3") (pintype "power_in"))
    )
    (net (code "43") (name "VDDD") (class "Default")
      (node (ref "C38") (pin "1") (pinfunction "1_1") (pintype "passive"))
      (node (ref "C39") (pin "1") (pinfunction "1_1") (pintype "passive"))
      (node (ref "C40") (pin "2") (pinfunction "2_2") (pintype "passive"))
      (node (ref "R25") (pin "2") (pinfunction "2_2") (pintype "passive"))
      (node (ref "R26") (pin "2") (pinfunction "2_2") (pintype "passive"))
      (node (ref "U1") (pin "23") (pinfunction "VDDD_23") (pintype "power_in"))
    )
    (net (code "44") (name "VREF") (class "Default")
      (node (ref "C34") (pin "1") (pinfunction "1_1") (pintype "passive"))
      (node (ref "D4") (pin "1") (pinfunction "A_1") (pintype "passive"))
      (node (ref "R21") (pin "2") (pinfunction "2_2") (pintype "passive"))
      (node (ref "R22") (pin "2") (pinfunction "2_2") (pintype "passive"))
      (node (ref "R23") (pin "2") (pinfunction "2_2") (pintype "passive"))
      (node (ref "R24") (pin "2") (pinfunction "2_2") (pintype "passive"))
      (node (ref "TP19") (pin "1") (pinfunction "1_1") (pintype "passive"))
      (node (ref "U2") (pin "12") (pinfunction "VREF_12") (pintype "output"))
    )
    (net (code "45") (name "unconnected-(J3-SBU1-PadA8)") (class "Default")
      (node (ref "J3") (pin "A8") (pinfunction "SBU1_A8") (pintype "bidirectional+no_connect"))
    )
    (net (code "46") (name "unconnected-(J3-SBU2-PadB8)") (class "Default")
      (node (ref "J3") (pin "B8") (pinfunction "SBU2_B8") (pintype "bidirectional+no_connect"))
    )
    (net (code "47") (name "unconnected-(U1A-D+-Pad17)") (class "Default")
      (node (ref "U1") (pin "17") (pinfunction "D+_17") (pintype "passive+no_connect"))
    )
    (net (code "48") (name "unconnected-(U1A-D--Pad16)") (class "Default")
      (node (ref "U1") (pin "16") (pinfunction "D-_16") (pintype "passive+no_connect"))
    )
    (net (code "49") (name "unconnected-(U1A-DNU1-Pad20)") (class "Default")
      (node (ref "U1") (pin "20") (pinfunction "DNU1_20") (pintype "bidirectional+no_connect"))
    )
    (net (code "50") (name "unconnected-(U1A-DNU2-Pad21)") (class "Default")
      (node (ref "U1") (pin "21") (pinfunction "DNU2_21") (pintype "bidirectional+no_connect"))
    )
    (net (code "51") (name "unconnected-(U1A-GPIO_1-Pad8)") (class "Default")
      (node (ref "U1") (pin "8") (pinfunction "GPIO_1_8") (pintype "passive+no_connect"))
    )
    (net (code "52") (name "unconnected-(U1A-HPI_INT-Pad7)") (class "Default")
      (node (ref "U1") (pin "7") (pinfunction "HPI_INT_7") (pintype "passive+no_connect"))
    )
    (net (code "53") (name "unconnected-(U1A-SAFE_PWR_EN-Pad4)") (class "Default")
      (node (ref "U1") (pin "4") (pinfunction "SAFE_PWR_EN_4") (pintype "passive+no_connect"))
    )
    (net (code "54") (name "unconnected-(U2-ACDRV-Pad8)") (class "Default")
      (node (ref "U2") (pin "8") (pinfunction "ACDRV_8") (pintype "passive+no_connect"))
    )
    (net (code "55") (name "unconnected-(U2-CELL-Pad14)") (class "Default")
      (node (ref "U2") (pin "14") (pinfunction "CELL_14") (pintype "passive+no_connect"))
    )
    (net (code "56") (name "unconnected-(U2-CMSRC-Pad7)") (class "Default")
      (node (ref "U2") (pin "7") (pinfunction "CMSRC_7") (pintype "passive+no_connect"))
    )
  )
)
